# TDA7439DS.net
KiCad netlist of a schematic drawn in Altium Designer
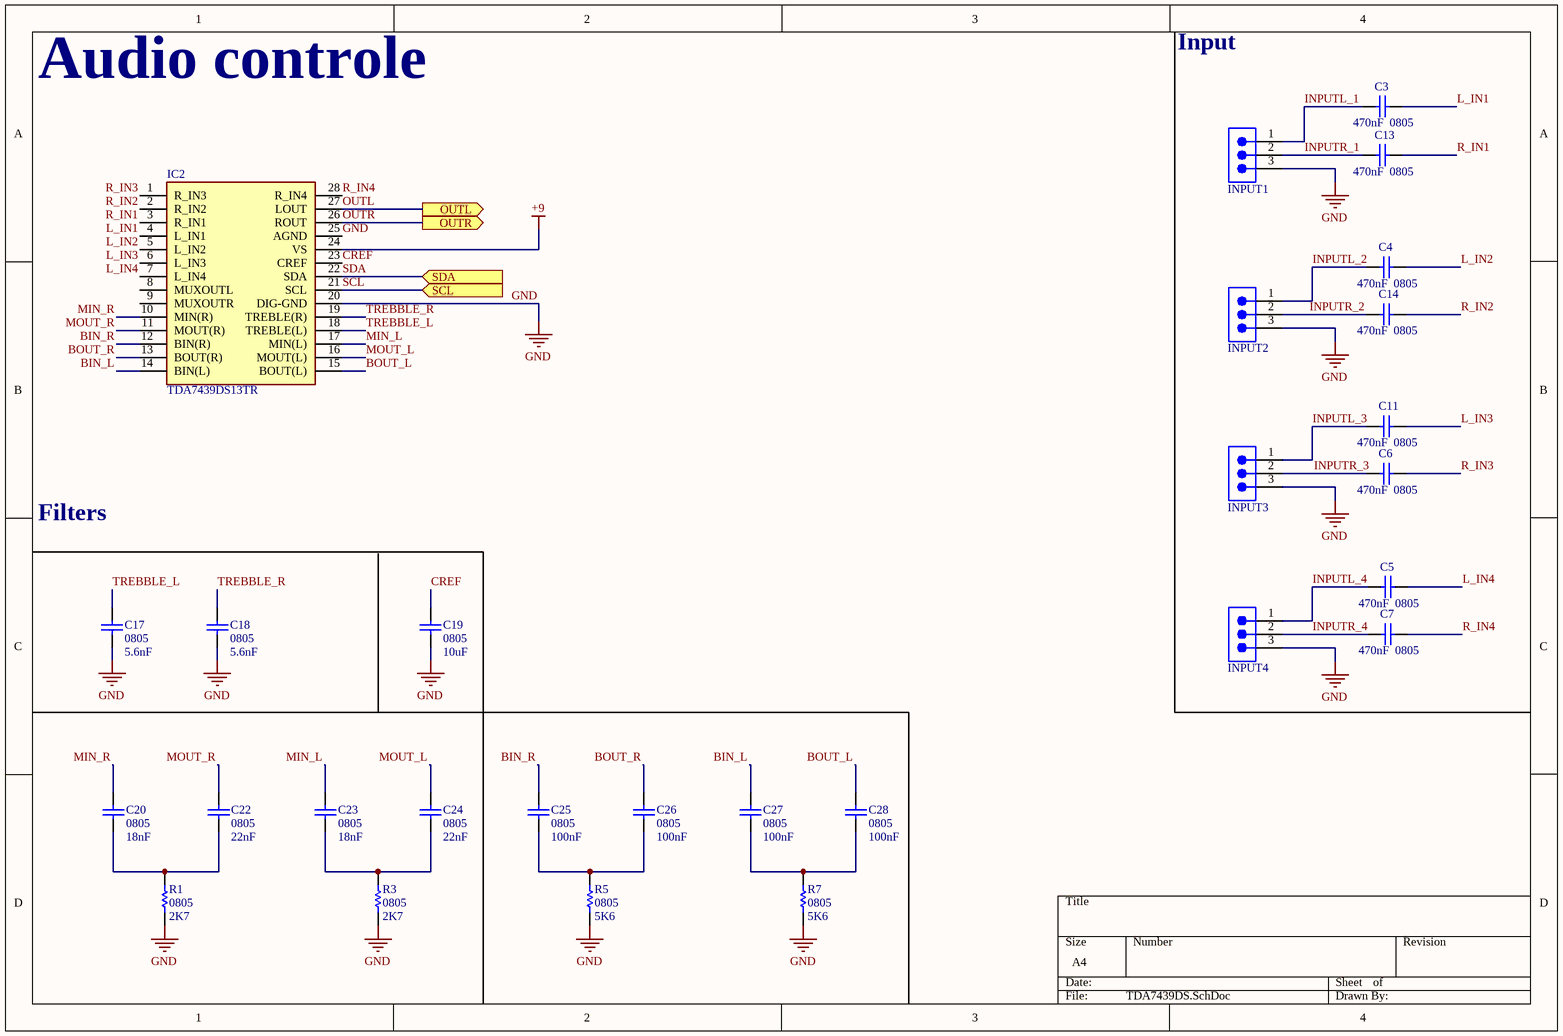
[diagram p0: TDA7439DS.SchDoc]

(export (version "E")
  (design (tool "Eeschema 10.0.6"))
  (components
    (comp (ref "C3")
      (value "0805")
      (footprint "6-0805_N")
      (description "Capacitor")
      (fields (field (name "ALTIUM_VALUE") "470nF") (field (name "PUBLISHER") "Altium Limited"))
      (libsource (lib "Miscellaneous Devices") (part "Cap"))
    )
    (comp (ref "C4")
      (value "0805")
      (footprint "6-0805_N")
      (description "Capacitor")
      (fields (field (name "ALTIUM_VALUE") "470nF") (field (name "PUBLISHER") "Altium Limited"))
      (libsource (lib "Miscellaneous Devices") (part "Cap"))
    )
    (comp (ref "C5")
      (value "0805")
      (footprint "6-0805_N")
      (description "Capacitor")
      (fields (field (name "ALTIUM_VALUE") "470nF") (field (name "PUBLISHER") "Altium Limited"))
      (libsource (lib "Miscellaneous Devices") (part "Cap"))
    )
    (comp (ref "C6")
      (value "0805")
      (footprint "6-0805_N")
      (description "Capacitor")
      (fields (field (name "ALTIUM_VALUE") "470nF") (field (name "PUBLISHER") "Altium Limited"))
      (libsource (lib "Miscellaneous Devices") (part "Cap"))
    )
    (comp (ref "C7")
      (value "0805")
      (footprint "6-0805_N")
      (description "Capacitor")
      (fields (field (name "ALTIUM_VALUE") "470nF") (field (name "PUBLISHER") "Altium Limited"))
      (libsource (lib "Miscellaneous Devices") (part "Cap"))
    )
    (comp (ref "C11")
      (value "0805")
      (footprint "6-0805_N")
      (description "Capacitor")
      (fields (field (name "ALTIUM_VALUE") "470nF") (field (name "PUBLISHER") "Altium Limited"))
      (libsource (lib "Miscellaneous Devices") (part "Cap"))
    )
    (comp (ref "C13")
      (value "0805")
      (footprint "6-0805_N")
      (description "Capacitor")
      (fields (field (name "ALTIUM_VALUE") "470nF") (field (name "PUBLISHER") "Altium Limited"))
      (libsource (lib "Miscellaneous Devices") (part "Cap"))
    )
    (comp (ref "C14")
      (value "0805")
      (footprint "6-0805_N")
      (description "Capacitor")
      (fields (field (name "ALTIUM_VALUE") "470nF") (field (name "PUBLISHER") "Altium Limited"))
      (libsource (lib "Miscellaneous Devices") (part "Cap"))
    )
    (comp (ref "C17")
      (value "0805")
      (footprint "6-0805_N")
      (description "Capacitor")
      (fields (field (name "ALTIUM_VALUE") "5.6nF") (field (name "PUBLISHER") "Altium Limited"))
      (libsource (lib "Miscellaneous Devices") (part "Cap"))
    )
    (comp (ref "C18")
      (value "0805")
      (footprint "6-0805_N")
      (description "Capacitor")
      (fields (field (name "ALTIUM_VALUE") "5.6nF") (field (name "PUBLISHER") "Altium Limited"))
      (libsource (lib "Miscellaneous Devices") (part "Cap"))
    )
    (comp (ref "C19")
      (value "0805")
      (footprint "6-0805_N")
      (description "Capacitor")
      (fields (field (name "ALTIUM_VALUE") "10uF") (field (name "PUBLISHER") "Altium Limited"))
      (libsource (lib "Miscellaneous Devices") (part "Cap"))
    )
    (comp (ref "C20")
      (value "0805")
      (footprint "6-0805_N")
      (description "Capacitor")
      (fields (field (name "ALTIUM_VALUE") "18nF") (field (name "PUBLISHER") "Altium Limited"))
      (libsource (lib "Miscellaneous Devices") (part "Cap"))
    )
    (comp (ref "C22")
      (value "0805")
      (footprint "6-0805_N")
      (description "Capacitor")
      (fields (field (name "ALTIUM_VALUE") "22nF") (field (name "PUBLISHER") "Altium Limited"))
      (libsource (lib "Miscellaneous Devices") (part "Cap"))
    )
    (comp (ref "C23")
      (value "0805")
      (footprint "6-0805_N")
      (description "Capacitor")
      (fields (field (name "ALTIUM_VALUE") "18nF") (field (name "PUBLISHER") "Altium Limited"))
      (libsource (lib "Miscellaneous Devices") (part "Cap"))
    )
    (comp (ref "C24")
      (value "0805")
      (footprint "6-0805_N")
      (description "Capacitor")
      (fields (field (name "ALTIUM_VALUE") "22nF") (field (name "PUBLISHER") "Altium Limited"))
      (libsource (lib "Miscellaneous Devices") (part "Cap"))
    )
    (comp (ref "C25")
      (value "0805")
      (footprint "6-0805_N")
      (description "Capacitor")
      (fields (field (name "ALTIUM_VALUE") "100nF") (field (name "PUBLISHER") "Altium Limited"))
      (libsource (lib "Miscellaneous Devices") (part "Cap"))
    )
    (comp (ref "C26")
      (value "0805")
      (footprint "6-0805_N")
      (description "Capacitor")
      (fields (field (name "ALTIUM_VALUE") "100nF") (field (name "PUBLISHER") "Altium Limited"))
      (libsource (lib "Miscellaneous Devices") (part "Cap"))
    )
    (comp (ref "C27")
      (value "0805")
      (footprint "6-0805_N")
      (description "Capacitor")
      (fields (field (name "ALTIUM_VALUE") "100nF") (field (name "PUBLISHER") "Altium Limited"))
      (libsource (lib "Miscellaneous Devices") (part "Cap"))
    )
    (comp (ref "C28")
      (value "0805")
      (footprint "6-0805_N")
      (description "Capacitor")
      (fields (field (name "ALTIUM_VALUE") "100nF") (field (name "PUBLISHER") "Altium Limited"))
      (libsource (lib "Miscellaneous Devices") (part "Cap"))
    )
    (comp (ref "IC2")
      (value "TDA7439DS13TR")
      (footprint "SamacSys:SOIC127P1032X265-28N")
      (description "Integrated Circuit")
      (fields (field (name "MOUSER2 PART NUMBER") "511-TDA7439DS13TR"))
      (libsource (lib "SamacSys") (part "TDA7439DS13TR"))
    )
    (comp (ref "INPUT1")
      (value "TSW-103-07-F-S")
      (footprint "SMTC-TSW-103-07-X-S")
      (description "0.025\" SQ Post Header, Through-hole, Vertical, -55 to 125 degC, 2.54 mm Pitch, 3-Pin, Male, RoHS")
      (fields (field (name "MANUFACTURER") "Samtec"))
      (libsource (lib "Altium Content Vault") (part "SMTC-TSW-103-X-X-S-X"))
    )
    (comp (ref "INPUT2")
      (value "TSW-103-07-F-S")
      (footprint "SMTC-TSW-103-07-X-S")
      (description "0.025\" SQ Post Header, Through-hole, Vertical, -55 to 125 degC, 2.54 mm Pitch, 3-Pin, Male, RoHS")
      (fields (field (name "MANUFACTURER") "Samtec"))
      (libsource (lib "Altium Content Vault") (part "SMTC-TSW-103-X-X-S-X"))
    )
    (comp (ref "INPUT3")
      (value "TSW-103-07-F-S")
      (footprint "SMTC-TSW-103-07-X-S")
      (description "0.025\" SQ Post Header, Through-hole, Vertical, -55 to 125 degC, 2.54 mm Pitch, 3-Pin, Male, RoHS")
      (fields (field (name "MANUFACTURER") "Samtec"))
      (libsource (lib "Altium Content Vault") (part "SMTC-TSW-103-X-X-S-X"))
    )
    (comp (ref "INPUT4")
      (value "TSW-103-07-F-S")
      (footprint "SMTC-TSW-103-07-X-S")
      (description "0.025\" SQ Post Header, Through-hole, Vertical, -55 to 125 degC, 2.54 mm Pitch, 3-Pin, Male, RoHS")
      (fields (field (name "MANUFACTURER") "Samtec"))
      (libsource (lib "Altium Content Vault") (part "SMTC-TSW-103-X-X-S-X"))
    )
    (comp (ref "R1")
      (value "0805")
      (footprint "6-0805_N")
      (description "Resistor")
      (fields (field (name "ALTIUM_VALUE") "2K7") (field (name "PUBLISHER") "Altium Limited"))
      (libsource (lib "Miscellaneous Devices") (part "Res1"))
    )
    (comp (ref "R3")
      (value "0805")
      (footprint "6-0805_N")
      (description "Resistor")
      (fields (field (name "ALTIUM_VALUE") "2K7") (field (name "PUBLISHER") "Altium Limited"))
      (libsource (lib "Miscellaneous Devices") (part "Res1"))
    )
    (comp (ref "R5")
      (value "0805")
      (footprint "6-0805_N")
      (description "Resistor")
      (fields (field (name "ALTIUM_VALUE") "5K6") (field (name "PUBLISHER") "Altium Limited"))
      (libsource (lib "Miscellaneous Devices") (part "Res1"))
    )
    (comp (ref "R7")
      (value "0805")
      (footprint "6-0805_N")
      (description "Resistor")
      (fields (field (name "ALTIUM_VALUE") "5K6") (field (name "PUBLISHER") "Altium Limited"))
      (libsource (lib "Miscellaneous Devices") (part "Res1"))
    )
  )
  (nets
    (net (code "1") (name "+9") (class "Default")
      (node (ref "IC2") (pin "24") (pinfunction "VS_24") (pintype "passive"))
    )
    (net (code "2") (name "/BIN_L") (class "Default")
      (node (ref "C27") (pin "1") (pinfunction "1_1") (pintype "passive"))
      (node (ref "IC2") (pin "14") (pinfunction "BIN(L)_14") (pintype "passive"))
    )
    (net (code "3") (name "/BIN_R") (class "Default")
      (node (ref "C25") (pin "1") (pinfunction "1_1") (pintype "passive"))
      (node (ref "IC2") (pin "12") (pinfunction "BIN(R)_12") (pintype "passive"))
    )
    (net (code "4") (name "/BOUT_L") (class "Default")
      (node (ref "C28") (pin "1") (pinfunction "1_1") (pintype "passive"))
      (node (ref "IC2") (pin "15") (pinfunction "BOUT(L)_15") (pintype "passive"))
    )
    (net (code "5") (name "/BOUT_R") (class "Default")
      (node (ref "C26") (pin "1") (pinfunction "1_1") (pintype "passive"))
      (node (ref "IC2") (pin "13") (pinfunction "BOUT(R)_13") (pintype "passive"))
    )
    (net (code "6") (name "/CREF") (class "Default")
      (node (ref "C19") (pin "1") (pinfunction "1_1") (pintype "passive"))
      (node (ref "IC2") (pin "23") (pinfunction "CREF_23") (pintype "passive"))
    )
    (net (code "7") (name "/INPUTL_1") (class "Default")
      (node (ref "C3") (pin "1") (pinfunction "1_1") (pintype "passive"))
      (node (ref "INPUT1") (pin "1") (pinfunction "1_1") (pintype "passive"))
    )
    (net (code "8") (name "/INPUTL_2") (class "Default")
      (node (ref "C4") (pin "1") (pinfunction "1_1") (pintype "passive"))
      (node (ref "INPUT2") (pin "1") (pinfunction "1_1") (pintype "passive"))
    )
    (net (code "9") (name "/INPUTL_3") (class "Default")
      (node (ref "C11") (pin "1") (pinfunction "1_1") (pintype "passive"))
      (node (ref "INPUT3") (pin "1") (pinfunction "1_1") (pintype "passive"))
    )
    (net (code "10") (name "/INPUTL_4") (class "Default")
      (node (ref "C5") (pin "1") (pinfunction "1_1") (pintype "passive"))
      (node (ref "INPUT4") (pin "1") (pinfunction "1_1") (pintype "passive"))
    )
    (net (code "11") (name "/INPUTR_1") (class "Default")
      (node (ref "C13") (pin "1") (pinfunction "1_1") (pintype "passive"))
      (node (ref "INPUT1") (pin "2") (pinfunction "2_2") (pintype "passive"))
    )
    (net (code "12") (name "/INPUTR_2") (class "Default")
      (node (ref "C14") (pin "1") (pinfunction "1_1") (pintype "passive"))
      (node (ref "INPUT2") (pin "2") (pinfunction "2_2") (pintype "passive"))
    )
    (net (code "13") (name "/INPUTR_3") (class "Default")
      (node (ref "C6") (pin "1") (pinfunction "1_1") (pintype "passive"))
      (node (ref "INPUT3") (pin "2") (pinfunction "2_2") (pintype "passive"))
    )
    (net (code "14") (name "/INPUTR_4") (class "Default")
      (node (ref "C7") (pin "1") (pinfunction "1_1") (pintype "passive"))
      (node (ref "INPUT4") (pin "2") (pinfunction "2_2") (pintype "passive"))
    )
    (net (code "15") (name "/L_IN1") (class "Default")
      (node (ref "C3") (pin "2") (pinfunction "2_2") (pintype "passive"))
      (node (ref "IC2") (pin "4") (pinfunction "L_IN1_4") (pintype "passive"))
    )
    (net (code "16") (name "/L_IN2") (class "Default")
      (node (ref "C4") (pin "2") (pinfunction "2_2") (pintype "passive"))
      (node (ref "IC2") (pin "5") (pinfunction "L_IN2_5") (pintype "passive"))
    )
    (net (code "17") (name "/L_IN3") (class "Default")
      (node (ref "C11") (pin "2") (pinfunction "2_2") (pintype "passive"))
      (node (ref "IC2") (pin "6") (pinfunction "L_IN3_6") (pintype "passive"))
    )
    (net (code "18") (name "/L_IN4") (class "Default")
      (node (ref "C5") (pin "2") (pinfunction "2_2") (pintype "passive"))
      (node (ref "IC2") (pin "7") (pinfunction "L_IN4_7") (pintype "passive"))
    )
    (net (code "19") (name "/MIN_L") (class "Default")
      (node (ref "C23") (pin "1") (pinfunction "1_1") (pintype "passive"))
      (node (ref "IC2") (pin "17") (pinfunction "MIN(L)_17") (pintype "passive"))
    )
    (net (code "20") (name "/MIN_R") (class "Default")
      (node (ref "C20") (pin "1") (pinfunction "1_1") (pintype "passive"))
      (node (ref "IC2") (pin "10") (pinfunction "MIN(R)_10") (pintype "passive"))
    )
    (net (code "21") (name "/MOUT_L") (class "Default")
      (node (ref "C24") (pin "1") (pinfunction "1_1") (pintype "passive"))
      (node (ref "IC2") (pin "16") (pinfunction "MOUT(L)_16") (pintype "passive"))
    )
    (net (code "22") (name "/MOUT_R") (class "Default")
      (node (ref "C22") (pin "1") (pinfunction "1_1") (pintype "passive"))
      (node (ref "IC2") (pin "11") (pinfunction "MOUT(R)_11") (pintype "passive"))
    )
    (net (code "23") (name "/OUTL") (class "Default")
      (node (ref "IC2") (pin "27") (pinfunction "LOUT_27") (pintype "passive"))
    )
    (net (code "24") (name "/OUTR") (class "Default")
      (node (ref "IC2") (pin "26") (pinfunction "ROUT_26") (pintype "passive"))
    )
    (net (code "25") (name "/R_IN1") (class "Default")
      (node (ref "C13") (pin "2") (pinfunction "2_2") (pintype "passive"))
      (node (ref "IC2") (pin "3") (pinfunction "R_IN1_3") (pintype "passive"))
    )
    (net (code "26") (name "/R_IN2") (class "Default")
      (node (ref "C14") (pin "2") (pinfunction "2_2") (pintype "passive"))
      (node (ref "IC2") (pin "2") (pinfunction "R_IN2_2") (pintype "passive"))
    )
    (net (code "27") (name "/R_IN3") (class "Default")
      (node (ref "C6") (pin "2") (pinfunction "2_2") (pintype "passive"))
      (node (ref "IC2") (pin "1") (pinfunction "R_IN3_1") (pintype "passive"))
    )
    (net (code "28") (name "/R_IN4") (class "Default")
      (node (ref "C7") (pin "2") (pinfunction "2_2") (pintype "passive"))
      (node (ref "IC2") (pin "28") (pinfunction "R_IN4_28") (pintype "passive"))
    )
    (net (code "29") (name "/SCL") (class "Default")
      (node (ref "IC2") (pin "21") (pinfunction "SCL_21") (pintype "passive"))
    )
    (net (code "30") (name "/SDA") (class "Default")
      (node (ref "IC2") (pin "22") (pinfunction "SDA_22") (pintype "passive"))
    )
    (net (code "31") (name "/TREBBLE_L") (class "Default")
      (node (ref "C17") (pin "1") (pinfunction "1_1") (pintype "passive"))
      (node (ref "IC2") (pin "18") (pinfunction "TREBLE(L)_18") (pintype "passive"))
    )
    (net (code "32") (name "/TREBBLE_R") (class "Default")
      (node (ref "C18") (pin "1") (pinfunction "1_1") (pintype "passive"))
      (node (ref "IC2") (pin "19") (pinfunction "TREBLE(R)_19") (pintype "passive"))
    )
    (net (code "33") (name "GND") (class "Default")
      (node (ref "C17") (pin "2") (pinfunction "2_2") (pintype "passive"))
      (node (ref "C18") (pin "2") (pinfunction "2_2") (pintype "passive"))
      (node (ref "C19") (pin "2") (pinfunction "2_2") (pintype "passive"))
      (node (ref "IC2") (pin "20") (pinfunction "DIG-GND_20") (pintype "passive"))
      (node (ref "IC2") (pin "25") (pinfunction "AGND_25") (pintype "passive"))
      (node (ref "INPUT1") (pin "3") (pinfunction "3_3") (pintype "passive"))
      (node (ref "INPUT2") (pin "3") (pinfunction "3_3") (pintype "passive"))
      (node (ref "INPUT3") (pin "3") (pinfunction "3_3") (pintype "passive"))
      (node (ref "INPUT4") (pin "3") (pinfunction "3_3") (pintype "passive"))
      (node (ref "R1") (pin "1") (pinfunction "1_1") (pintype "passive"))
      (node (ref "R3") (pin "1") (pinfunction "1_1") (pintype "passive"))
      (node (ref "R5") (pin "1") (pinfunction "1_1") (pintype "passive"))
      (node (ref "R7") (pin "1") (pinfunction "1_1") (pintype "passive"))
    )
    (net (code "34") (name "Net-(C20-Pad2)") (class "Default")
      (node (ref "C20") (pin "2") (pinfunction "2_2") (pintype "passive"))
      (node (ref "C22") (pin "2") (pinfunction "2_2") (pintype "passive"))
      (node (ref "R1") (pin "2") (pinfunction "2_2") (pintype "passive"))
    )
    (net (code "35") (name "Net-(C23-Pad2)") (class "Default")
      (node (ref "C23") (pin "2") (pinfunction "2_2") (pintype "passive"))
      (node (ref "C24") (pin "2") (pinfunction "2_2") (pintype "passive"))
      (node (ref "R3") (pin "2") (pinfunction "2_2") (pintype "passive"))
    )
    (net (code "36") (name "Net-(C25-Pad2)") (class "Default")
      (node (ref "C25") (pin "2") (pinfunction "2_2") (pintype "passive"))
      (node (ref "C26") (pin "2") (pinfunction "2_2") (pintype "passive"))
      (node (ref "R5") (pin "2") (pinfunction "2_2") (pintype "passive"))
    )
    (net (code "37") (name "Net-(C27-Pad2)") (class "Default")
      (node (ref "C27") (pin "2") (pinfunction "2_2") (pintype "passive"))
      (node (ref "C28") (pin "2") (pinfunction "2_2") (pintype "passive"))
      (node (ref "R7") (pin "2") (pinfunction "2_2") (pintype "passive"))
    )
    (net (code "38") (name "unconnected-(IC2-MUXOUTL-Pad8)") (class "Default")
      (node (ref "IC2") (pin "8") (pinfunction "MUXOUTL_8") (pintype "passive"))
    )
    (net (code "39") (name "unconnected-(IC2-MUXOUTR-Pad9)") (class "Default")
      (node (ref "IC2") (pin "9") (pinfunction "MUXOUTR_9") (pintype "passive"))
    )
  )
)
